# MEMS_BMI.net
KiCad netlist of a schematic drawn in EAGLE
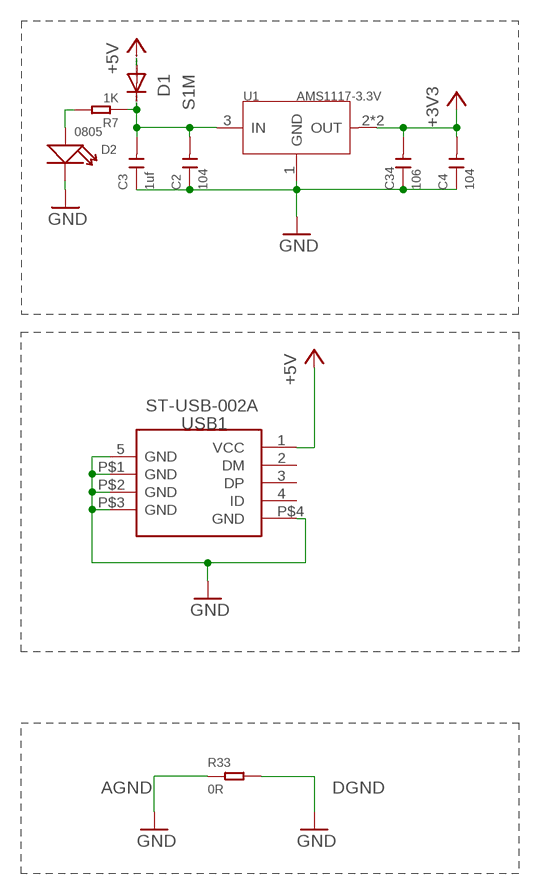
[diagram p0: schematic, sheet 1]
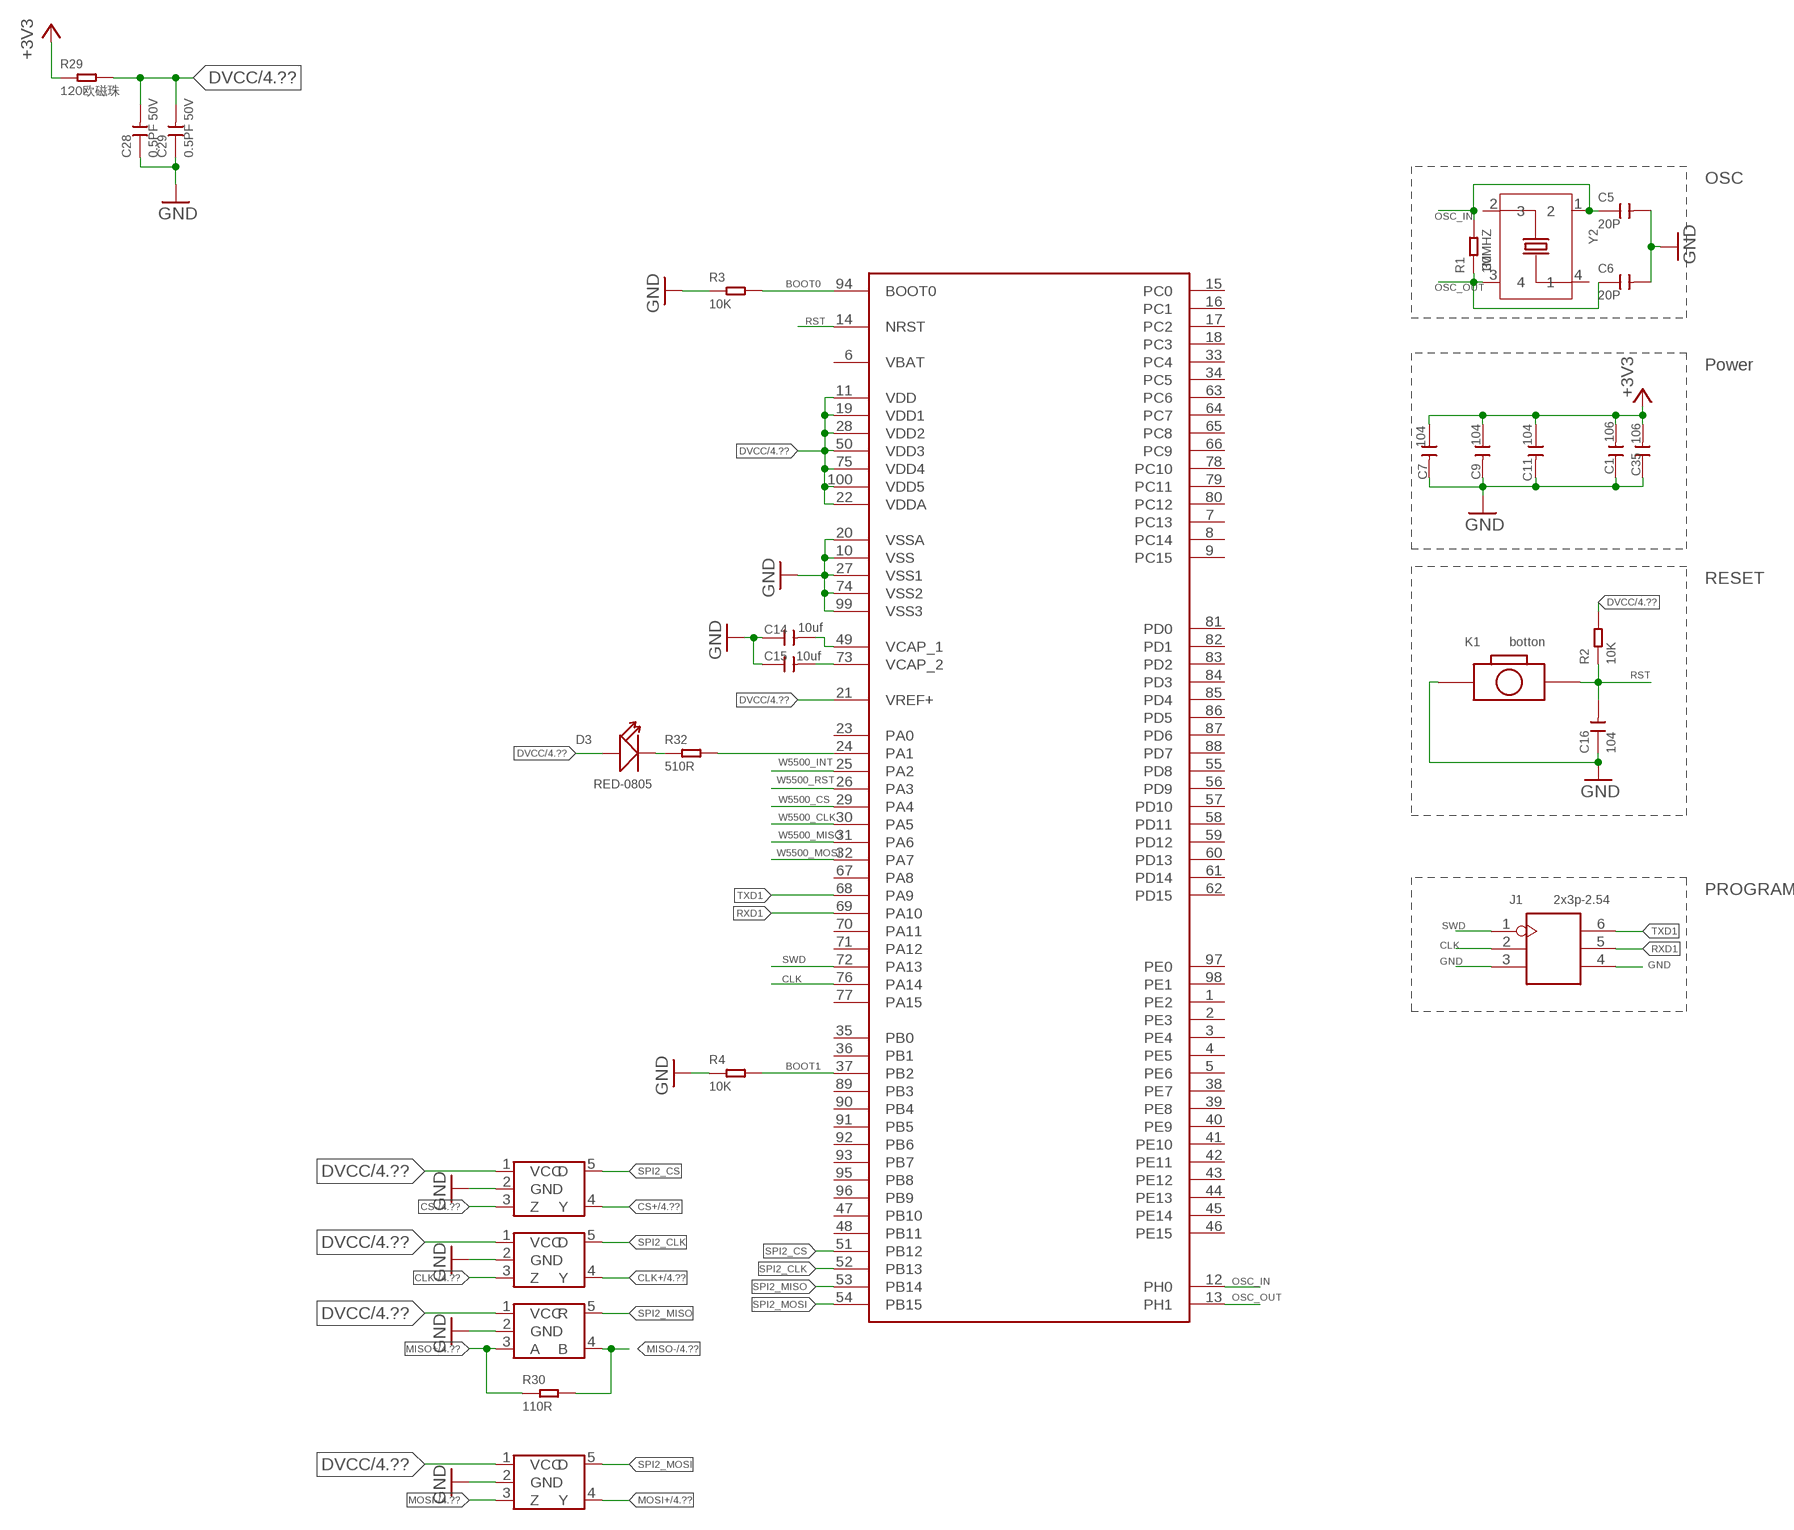
[diagram p1: schematic, sheet 2]
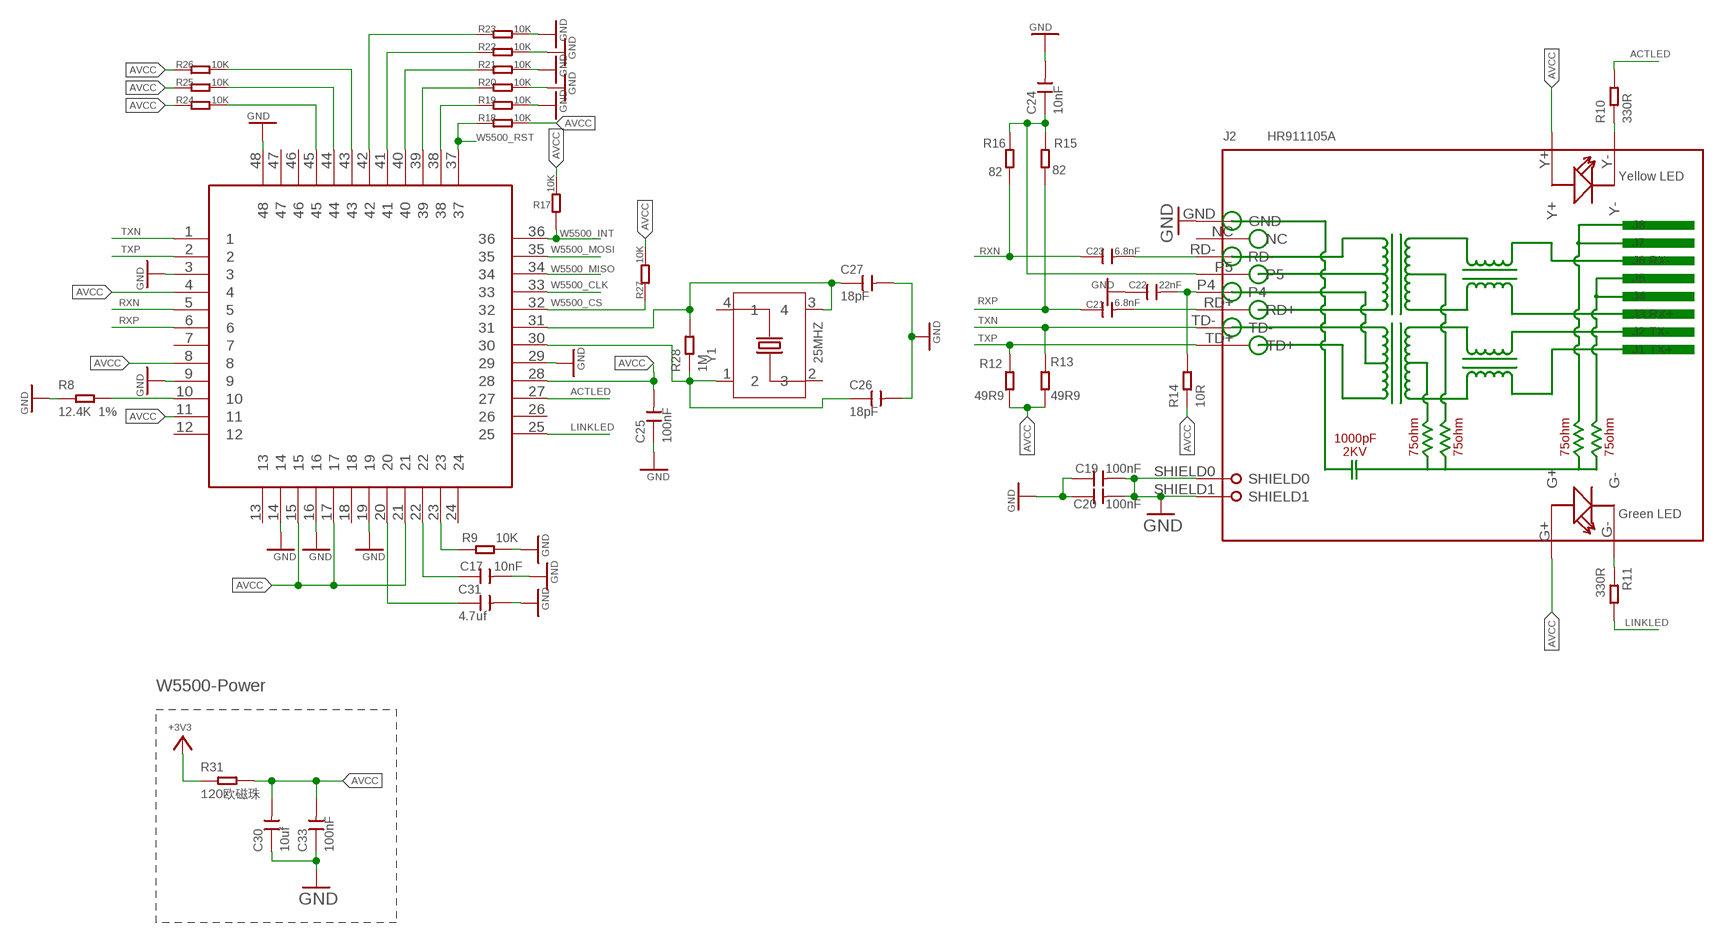
[diagram p2: schematic, sheet 3]
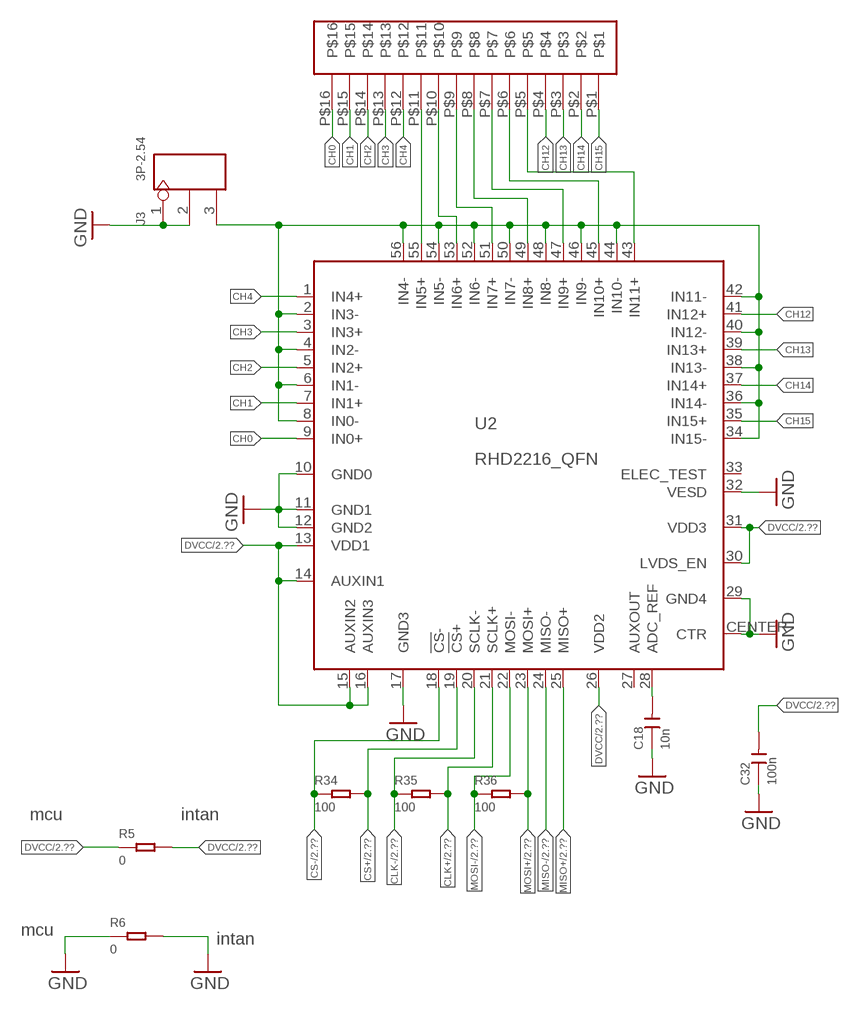
[diagram p3: schematic, sheet 4]

(export (version "E")
  (design (tool "Eeschema 10.0.6"))
  (components
    (comp (ref "C2")
      (value "104")
      (footprint "eagle-import:C0603")
      (libsource (lib "eagle-import") (part "CAP-(0603)"))
    )
    (comp (ref "C3")
      (value "1uf")
      (footprint "eagle-import:C0805")
      (fields (field (name "MPN") "CC0805KKX7R8BB105"))
      (libsource (lib "eagle-import") (part "CERAMIC-1UF-25V-10%-X7R(0805)"))
    )
    (comp (ref "C4")
      (value "104")
      (footprint "eagle-import:C0603")
      (libsource (lib "eagle-import") (part "CAP-(0603)"))
    )
    (comp (ref "C34")
      (value "106")
      (footprint "eagle-import:C0805")
      (fields (field (name "MPN") "CC0805KKX7R8BB105"))
      (libsource (lib "eagle-import") (part "CERAMIC-1UF-25V-10%-X7R(0805)"))
    )
    (comp (ref "D1")
      (value "S1M")
      (footprint "eagle-import:SMA")
      (libsource (lib "eagle-import") (part "S1M"))
    )
    (comp (ref "D2")
      (value "0805")
      (footprint "eagle-import:LED-0805")
      (fields (field (name "MPN") "17-215SURC/S530-A2/TR8"))
      (libsource (lib "eagle-import") (part "SMD-LED-CLEAR-RED(0805)"))
    )
    (comp (ref "R7")
      (value "1K")
      (footprint "eagle-import:R0603")
      (fields (field (name "MPN") "RC0603FR-071M1L"))
      (libsource (lib "eagle-import") (part "RES-(0603)"))
    )
    (comp (ref "R33")
      (value "0R")
      (footprint "eagle-import:R0603")
      (fields (field (name "MPN") "RC0603FR-071M1L"))
      (libsource (lib "eagle-import") (part "RES-(0603)"))
    )
    (comp (ref "U1")
      (value "AMS1117-3.3V")
      (footprint "eagle-import:SOT-223")
      (fields (field (name "MPN") "CJT1117-3.3"))
      (libsource (lib "eagle-import") (part "PMIC-CJT1117-3.3(SOT223)"))
    )
    (comp (ref "USB1")
      (value "ST-USB-002A")
      (footprint "eagle-import:MINIUSB5+4P-SMD-0.8-90D")
      (libsource (lib "eagle-import") (part "MINI-USB-RCPT-B-5PS-R/A-SMD(ST-USB-002A)"))
    )
    (comp (ref "C18")
      (value "10n")
      (footprint "eagle-import:C0603")
      (libsource (lib "eagle-import") (part "CAP-(0603)"))
    )
    (comp (ref "C32")
      (value "100n")
      (footprint "eagle-import:C0603")
      (libsource (lib "eagle-import") (part "CAP-(0603)"))
    )
    (comp (ref "J3")
      (value "3P-2.54")
      (footprint "eagle-import:H3-2.54")
      (fields (field (name "MPN") "P125-1103A0BS116A1"))
      (libsource (lib "eagle-import") (part "DIP-WHITE-MALE-HEADER-VERT(3P-2.54)"))
    )
    (comp (ref "R5")
      (value "0")
      (footprint "eagle-import:R0603")
      (fields (field (name "MPN") "RC0603FR-071M1L"))
      (libsource (lib "eagle-import") (part "RES-(0603)"))
    )
    (comp (ref "R6")
      (value "0")
      (footprint "eagle-import:R0603")
      (fields (field (name "MPN") "RC0603FR-071M1L"))
      (libsource (lib "eagle-import") (part "RES-(0603)"))
    )
    (comp (ref "R34")
      (value "100")
      (footprint "eagle-import:R0603")
      (fields (field (name "MPN") "RC0603FR-071M1L"))
      (libsource (lib "eagle-import") (part "RES-(0603)"))
    )
    (comp (ref "R35")
      (value "100")
      (footprint "eagle-import:R0603")
      (fields (field (name "MPN") "RC0603FR-071M1L"))
      (libsource (lib "eagle-import") (part "RES-(0603)"))
    )
    (comp (ref "R36")
      (value "100")
      (footprint "eagle-import:R0603")
      (fields (field (name "MPN") "RC0603FR-071M1L"))
      (libsource (lib "eagle-import") (part "RES-(0603)"))
    )
    (comp (ref "U$3")
      (value "PROBE")
      (footprint "eagle-import:PROBE-16-PIN")
      (libsource (lib "eagle-import") (part "PROBE"))
    )
    (comp (ref "U2")
      (value "RHD2216_QFN")
      (footprint "eagle-import:QFN56_8_X_8_LARGE")
      (libsource (lib "eagle-import") (part "RHD2216_QFN"))
    )
    (comp (ref "C17")
      (value "10nF")
      (footprint "eagle-import:C0603")
      (libsource (lib "eagle-import") (part "CAP-(0603)"))
    )
    (comp (ref "C19")
      (value "100nF")
      (footprint "eagle-import:C0603")
      (libsource (lib "eagle-import") (part "CAP-(0603)"))
    )
    (comp (ref "C20")
      (value "100nF")
      (footprint "eagle-import:C0603")
      (libsource (lib "eagle-import") (part "CAP-(0603)"))
    )
    (comp (ref "C21")
      (value "6.8nF")
      (footprint "eagle-import:C0603")
      (libsource (lib "eagle-import") (part "CAP-(0603)"))
    )
    (comp (ref "C22")
      (value "22nF")
      (footprint "eagle-import:C0603")
      (libsource (lib "eagle-import") (part "CAP-(0603)"))
    )
    (comp (ref "C23")
      (value "6.8nF")
      (footprint "eagle-import:C0603")
      (libsource (lib "eagle-import") (part "CAP-(0603)"))
    )
    (comp (ref "C24")
      (value "10nF")
      (footprint "eagle-import:C0603")
      (libsource (lib "eagle-import") (part "CAP-(0603)"))
    )
    (comp (ref "C25")
      (value "100nF")
      (footprint "eagle-import:C0603")
      (libsource (lib "eagle-import") (part "CAP-(0603)"))
    )
    (comp (ref "C26")
      (value "18pF")
      (footprint "eagle-import:C0603")
      (libsource (lib "eagle-import") (part "CAP-(0603)"))
    )
    (comp (ref "C27")
      (value "18pF")
      (footprint "eagle-import:C0603")
      (libsource (lib "eagle-import") (part "CAP-(0603)"))
    )
    (comp (ref "C30")
      (value "10uf")
      (footprint "eagle-import:C0805")
      (fields (field (name "MPN") "CC0805KKX7R8BB105"))
      (libsource (lib "eagle-import") (part "CERAMIC-1UF-25V-10%-X7R(0805)"))
    )
    (comp (ref "C31")
      (value "4.7uf")
      (footprint "eagle-import:C0805")
      (fields (field (name "MPN") "CC0805KKX7R8BB105"))
      (libsource (lib "eagle-import") (part "CERAMIC-1UF-25V-10%-X7R(0805)"))
    )
    (comp (ref "C33")
      (value "100nF")
      (footprint "eagle-import:C0603")
      (libsource (lib "eagle-import") (part "CAP-(0603)"))
    )
    (comp (ref "J2")
      (value "HR911105A")
      (footprint "eagle-import:RJ45-12+2P-21.3X16.04X13.4MM")
      (libsource (lib "eagle-import") (part "DIP-RJ45-CONNECTOR(HR911105A)"))
    )
    (comp (ref "R8")
      (value "12.4K 1%")
      (footprint "eagle-import:R0603")
      (fields (field (name "MPN") "RC0603FR-071M1L"))
      (libsource (lib "eagle-import") (part "RES-(0603)"))
    )
    (comp (ref "R9")
      (value "10K")
      (footprint "eagle-import:R0603")
      (fields (field (name "MPN") "RC0603FR-071M1L"))
      (libsource (lib "eagle-import") (part "RES-(0603)"))
    )
    (comp (ref "R10")
      (value "330R")
      (footprint "eagle-import:R0603")
      (fields (field (name "MPN") "RC0603FR-071M1L"))
      (libsource (lib "eagle-import") (part "RES-(0603)"))
    )
    (comp (ref "R11")
      (value "330R")
      (footprint "eagle-import:R0603")
      (fields (field (name "MPN") "RC0603FR-071M1L"))
      (libsource (lib "eagle-import") (part "RES-(0603)"))
    )
    (comp (ref "R12")
      (value "49R9")
      (footprint "eagle-import:R0603")
      (fields (field (name "MPN") "RC0603FR-071M1L"))
      (libsource (lib "eagle-import") (part "RES-(0603)"))
    )
    (comp (ref "R13")
      (value "49R9")
      (footprint "eagle-import:R0603")
      (fields (field (name "MPN") "RC0603FR-071M1L"))
      (libsource (lib "eagle-import") (part "RES-(0603)"))
    )
    (comp (ref "R14")
      (value "10R")
      (footprint "eagle-import:R0603")
      (fields (field (name "MPN") "RC0603FR-071M1L"))
      (libsource (lib "eagle-import") (part "RES-(0603)"))
    )
    (comp (ref "R15")
      (value "82")
      (footprint "eagle-import:R0603")
      (fields (field (name "MPN") "RC0603FR-071M1L"))
      (libsource (lib "eagle-import") (part "RES-(0603)"))
    )
    (comp (ref "R16")
      (value "82")
      (footprint "eagle-import:R0603")
      (fields (field (name "MPN") "RC0603FR-071M1L"))
      (libsource (lib "eagle-import") (part "RES-(0603)"))
    )
    (comp (ref "R17")
      (value "10K")
      (footprint "eagle-import:R0603")
      (fields (field (name "MPN") "RC0603FR-071M1L"))
      (libsource (lib "eagle-import") (part "RES-(0603)"))
    )
    (comp (ref "R18")
      (value "10K")
      (footprint "eagle-import:R0603")
      (fields (field (name "MPN") "RC0603FR-071M1L"))
      (libsource (lib "eagle-import") (part "RES-(0603)"))
    )
    (comp (ref "R19")
      (value "10K")
      (footprint "eagle-import:R0603")
      (fields (field (name "MPN") "RC0603FR-071M1L"))
      (libsource (lib "eagle-import") (part "RES-(0603)"))
    )
    (comp (ref "R20")
      (value "10K")
      (footprint "eagle-import:R0603")
      (fields (field (name "MPN") "RC0603FR-071M1L"))
      (libsource (lib "eagle-import") (part "RES-(0603)"))
    )
    (comp (ref "R21")
      (value "10K")
      (footprint "eagle-import:R0603")
      (fields (field (name "MPN") "RC0603FR-071M1L"))
      (libsource (lib "eagle-import") (part "RES-(0603)"))
    )
    (comp (ref "R22")
      (value "10K")
      (footprint "eagle-import:R0603")
      (fields (field (name "MPN") "RC0603FR-071M1L"))
      (libsource (lib "eagle-import") (part "RES-(0603)"))
    )
    (comp (ref "R23")
      (value "10K")
      (footprint "eagle-import:R0603")
      (fields (field (name "MPN") "RC0603FR-071M1L"))
      (libsource (lib "eagle-import") (part "RES-(0603)"))
    )
    (comp (ref "R24")
      (value "10K")
      (footprint "eagle-import:R0603")
      (fields (field (name "MPN") "RC0603FR-071M1L"))
      (libsource (lib "eagle-import") (part "RES-(0603)"))
    )
    (comp (ref "R25")
      (value "10K")
      (footprint "eagle-import:R0603")
      (fields (field (name "MPN") "RC0603FR-071M1L"))
      (libsource (lib "eagle-import") (part "RES-(0603)"))
    )
    (comp (ref "R26")
      (value "10K")
      (footprint "eagle-import:R0603")
      (fields (field (name "MPN") "RC0603FR-071M1L"))
      (libsource (lib "eagle-import") (part "RES-(0603)"))
    )
    (comp (ref "R27")
      (value "10K")
      (footprint "eagle-import:R0603")
      (fields (field (name "MPN") "RC0603FR-071M1L"))
      (libsource (lib "eagle-import") (part "RES-(0603)"))
    )
    (comp (ref "R28")
      (value "1M")
      (footprint "eagle-import:R0603")
      (fields (field (name "MPN") "RC0603FR-071M1L"))
      (libsource (lib "eagle-import") (part "RES-(0603)"))
    )
    (comp (ref "R31")
      (value "120欧磁珠")
      (footprint "eagle-import:R0603")
      (fields (field (name "MPN") "RC0603FR-071M1L"))
      (libsource (lib "eagle-import") (part "RES-(0603)"))
    )
    (comp (ref "W5500-1")
      (value "W5500")
      (footprint "eagle-import:LQFP48")
      (libsource (lib "eagle-import") (part "W5500"))
    )
    (comp (ref "Y1")
      (value "25MHZ")
      (footprint "eagle-import:X4-SMD-3.2X2.5X0.7MM")
      (fields (field (name "MPN") "7M30000024"))
      (libsource (lib "eagle-import") (part "SMD-CRYSTAL-30MHZ-10PF-10PPM-60R(4P-3.2X2.5MM)"))
    )
    (comp (ref "C1")
      (value "106")
      (footprint "eagle-import:C0805")
      (fields (field (name "MPN") "CC0805KKX7R8BB105"))
      (libsource (lib "eagle-import") (part "CERAMIC-1UF-25V-10%-X7R(0805)"))
    )
    (comp (ref "C5")
      (value "20P")
      (footprint "eagle-import:C0603")
      (libsource (lib "eagle-import") (part "CAP-(0603)"))
    )
    (comp (ref "C6")
      (value "20P")
      (footprint "eagle-import:C0603")
      (libsource (lib "eagle-import") (part "CAP-(0603)"))
    )
    (comp (ref "C7")
      (value "104")
      (footprint "eagle-import:C0603")
      (libsource (lib "eagle-import") (part "CAP-(0603)"))
    )
    (comp (ref "C9")
      (value "104")
      (footprint "eagle-import:C0603")
      (libsource (lib "eagle-import") (part "CAP-(0603)"))
    )
    (comp (ref "C11")
      (value "104")
      (footprint "eagle-import:C0603")
      (libsource (lib "eagle-import") (part "CAP-(0603)"))
    )
    (comp (ref "C14")
      (value "10uf")
      (footprint "eagle-import:C0805")
      (fields (field (name "MPN") "CC0805KKX7R8BB105"))
      (libsource (lib "eagle-import") (part "CERAMIC-1UF-25V-10%-X7R(0805)"))
    )
    (comp (ref "C15")
      (value "10uf")
      (footprint "eagle-import:C0805")
      (fields (field (name "MPN") "CC0805KKX7R8BB105"))
      (libsource (lib "eagle-import") (part "CERAMIC-1UF-25V-10%-X7R(0805)"))
    )
    (comp (ref "C16")
      (value "104")
      (footprint "eagle-import:C0603")
      (libsource (lib "eagle-import") (part "CAP-(0603)"))
    )
    (comp (ref "C28")
      (value "0.5PF 50V")
      (footprint "eagle-import:C0603")
      (libsource (lib "eagle-import") (part "CAP-(0603)"))
    )
    (comp (ref "C29")
      (value "0.5PF 50V")
      (footprint "eagle-import:C0603")
      (libsource (lib "eagle-import") (part "CAP-(0603)"))
    )
    (comp (ref "C35")
      (value "106")
      (footprint "eagle-import:C0805")
      (fields (field (name "MPN") "CC0805KKX7R8BB105"))
      (libsource (lib "eagle-import") (part "CERAMIC-1UF-25V-10%-X7R(0805)"))
    )
    (comp (ref "D3")
      (value "RED-0805")
      (footprint "eagle-import:LED-0805")
      (fields (field (name "MPN") "17-215SURC/S530-A2/TR8"))
      (libsource (lib "eagle-import") (part "SMD-LED-CLEAR-RED(0805)"))
    )
    (comp (ref "J1")
      (value "2x3p-2.54")
      (footprint "eagle-import:H2X3-2.54")
      (fields (field (name "MPN") "F185-1203A1BSYA1"))
      (libsource (lib "eagle-import") (part "DIP-BLACK-FEMALE-HEADER-VERT(2X3P-2.54)"))
    )
    (comp (ref "K1")
      (value "botton")
      (footprint "eagle-import:SW2-SMD-3.0X6.0_2.5")
      (fields (field (name "MPN") "B3U-1000P"))
      (libsource (lib "eagle-import") (part "SMD-BUTTON"))
    )
    (comp (ref "LVDS1-1")
      (value "SN65LVDS1")
      (footprint "eagle-import:DBV_R-PDSO-G5")
      (libsource (lib "eagle-import") (part "SN65LVDS1"))
    )
    (comp (ref "LVDS1-2")
      (value "SN65LVDS1")
      (footprint "eagle-import:DBV_R-PDSO-G5")
      (libsource (lib "eagle-import") (part "SN65LVDS1"))
    )
    (comp (ref "LVDS1-3")
      (value "SN65LVDS1")
      (footprint "eagle-import:DBV_R-PDSO-G5")
      (libsource (lib "eagle-import") (part "SN65LVDS1"))
    )
    (comp (ref "R1")
      (value "1M")
      (footprint "eagle-import:R0603")
      (fields (field (name "MPN") "RC0603FR-071M1L"))
      (libsource (lib "eagle-import") (part "RES-(0603)"))
    )
    (comp (ref "R2")
      (value "10K")
      (footprint "eagle-import:R0603")
      (fields (field (name "MPN") "RC0603FR-071M1L"))
      (libsource (lib "eagle-import") (part "RES-(0603)"))
    )
    (comp (ref "R3")
      (value "10K")
      (footprint "eagle-import:R0603")
      (fields (field (name "MPN") "RC0603FR-071M1L"))
      (libsource (lib "eagle-import") (part "RES-(0603)"))
    )
    (comp (ref "R4")
      (value "10K")
      (footprint "eagle-import:R0603")
      (fields (field (name "MPN") "RC0603FR-071M1L"))
      (libsource (lib "eagle-import") (part "RES-(0603)"))
    )
    (comp (ref "R29")
      (value "120欧磁珠")
      (footprint "eagle-import:R0603")
      (fields (field (name "MPN") "RC0603FR-071M1L"))
      (libsource (lib "eagle-import") (part "RES-(0603)"))
    )
    (comp (ref "R30")
      (value "110R")
      (footprint "eagle-import:R0603")
      (fields (field (name "MPN") "RC0603FR-071M1L"))
      (libsource (lib "eagle-import") (part "RES-(0603)"))
    )
    (comp (ref "R32")
      (value "510R")
      (footprint "eagle-import:R0603")
      (fields (field (name "MPN") "RC0603FR-071M1L"))
      (libsource (lib "eagle-import") (part "RES-(0603)"))
    )
    (comp (ref "U$1")
      (value "STM32F40XSTM32D40X")
      (footprint "eagle-import:LQFP100")
      (libsource (lib "eagle-import") (part "STM32F40XSTM32D40X"))
    )
    (comp (ref "U$2")
      (value "SN65LVDS2")
      (footprint "eagle-import:DBV_R-PDSO-G5")
      (libsource (lib "eagle-import") (part "SN65LVDS2"))
    )
    (comp (ref "Y2")
      (value "30MHZ")
      (footprint "eagle-import:X4-SMD-3.2X2.5X0.7MM")
      (fields (field (name "MPN") "7M30000024"))
      (libsource (lib "eagle-import") (part "SMD-CRYSTAL-30MHZ-10PF-10PPM-60R(4P-3.2X2.5MM)"))
    )
  )
  (nets
    (net (code "1") (name "+3V3") (class "Default")
      (node (ref "C1") (pin "2") (pinfunction "2_2") (pintype "passive"))
      (node (ref "C11") (pin "1") (pinfunction "1_1") (pintype "passive"))
      (node (ref "C34") (pin "2") (pinfunction "2_2") (pintype "passive"))
      (node (ref "C35") (pin "2") (pinfunction "2_2") (pintype "passive"))
      (node (ref "C4") (pin "2") (pinfunction "2_2") (pintype "passive"))
      (node (ref "C7") (pin "1") (pinfunction "1_1") (pintype "passive"))
      (node (ref "C9") (pin "1") (pinfunction "1_1") (pintype "passive"))
      (node (ref "R29") (pin "1") (pinfunction "1_1") (pintype "passive"))
      (node (ref "R31") (pin "1") (pinfunction "1_1") (pintype "passive"))
      (node (ref "U1") (pin "2") (pinfunction "OUT_2") (pintype "bidirectional"))
      (node (ref "U1") (pin "TER") (pinfunction "OUT_TER") (pintype "bidirectional"))
    )
    (net (code "2") (name "+5V") (class "Default")
      (node (ref "D1") (pin "A") (pinfunction "A_A") (pintype "passive"))
      (node (ref "USB1") (pin "1") (pinfunction "VCC_1") (pintype "bidirectional"))
    )
    (net (code "3") (name "ACTLED") (class "Default")
      (node (ref "R10") (pin "2") (pinfunction "2_2") (pintype "passive"))
      (node (ref "W5500-1") (pin "27") (pinfunction "27_27") (pintype "bidirectional"))
    )
    (net (code "4") (name "AVCC") (class "Default")
      (node (ref "C25") (pin "2") (pinfunction "2_2") (pintype "passive"))
      (node (ref "C30") (pin "2") (pinfunction "2_2") (pintype "passive"))
      (node (ref "C33") (pin "2") (pinfunction "2_2") (pintype "passive"))
      (node (ref "J2") (pin "G+") (pinfunction "G+_G+") (pintype "bidirectional"))
      (node (ref "J2") (pin "Y+") (pinfunction "Y+_Y+") (pintype "bidirectional"))
      (node (ref "R12") (pin "1") (pinfunction "1_1") (pintype "passive"))
      (node (ref "R13") (pin "1") (pinfunction "1_1") (pintype "passive"))
      (node (ref "R14") (pin "1") (pinfunction "1_1") (pintype "passive"))
      (node (ref "R17") (pin "2") (pinfunction "2_2") (pintype "passive"))
      (node (ref "R18") (pin "2") (pinfunction "2_2") (pintype "passive"))
      (node (ref "R24") (pin "1") (pinfunction "1_1") (pintype "passive"))
      (node (ref "R25") (pin "1") (pinfunction "1_1") (pintype "passive"))
      (node (ref "R26") (pin "1") (pinfunction "1_1") (pintype "passive"))
      (node (ref "R27") (pin "2") (pinfunction "2_2") (pintype "passive"))
      (node (ref "R31") (pin "2") (pinfunction "2_2") (pintype "passive"))
      (node (ref "W5500-1") (pin "11") (pinfunction "11_11") (pintype "bidirectional"))
      (node (ref "W5500-1") (pin "15") (pinfunction "15_15") (pintype "bidirectional"))
      (node (ref "W5500-1") (pin "17") (pinfunction "17_17") (pintype "bidirectional"))
      (node (ref "W5500-1") (pin "21") (pinfunction "21_21") (pintype "bidirectional"))
      (node (ref "W5500-1") (pin "28") (pinfunction "28_28") (pintype "bidirectional"))
      (node (ref "W5500-1") (pin "4") (pinfunction "4_4") (pintype "bidirectional"))
      (node (ref "W5500-1") (pin "8") (pinfunction "8_8") (pintype "bidirectional"))
    )
    (net (code "5") (name "BOOT0") (class "Default")
      (node (ref "R3") (pin "2") (pinfunction "2_2") (pintype "passive"))
      (node (ref "U$1") (pin "94") (pinfunction "BOOT0_94") (pintype "bidirectional"))
    )
    (net (code "6") (name "BOOT1") (class "Default")
      (node (ref "R4") (pin "2") (pinfunction "2_2") (pintype "passive"))
      (node (ref "U$1") (pin "37") (pinfunction "PB2_37") (pintype "bidirectional"))
    )
    (net (code "7") (name "CH0") (class "Default")
      (node (ref "U$3") (pin "P$16") (pinfunction "P$16_P$16") (pintype "bidirectional"))
      (node (ref "U2") (pin "9") (pinfunction "IN0+_9") (pintype "input"))
    )
    (net (code "8") (name "CH1") (class "Default")
      (node (ref "U$3") (pin "P$15") (pinfunction "P$15_P$15") (pintype "bidirectional"))
      (node (ref "U2") (pin "7") (pinfunction "IN1+_7") (pintype "input"))
    )
    (net (code "9") (name "CH2") (class "Default")
      (node (ref "U$3") (pin "P$14") (pinfunction "P$14_P$14") (pintype "bidirectional"))
      (node (ref "U2") (pin "5") (pinfunction "IN2+_5") (pintype "input"))
    )
    (net (code "10") (name "CH3") (class "Default")
      (node (ref "U$3") (pin "P$13") (pinfunction "P$13_P$13") (pintype "bidirectional"))
      (node (ref "U2") (pin "3") (pinfunction "IN3+_3") (pintype "input"))
    )
    (net (code "11") (name "CH4") (class "Default")
      (node (ref "U$3") (pin "P$12") (pinfunction "P$12_P$12") (pintype "bidirectional"))
      (node (ref "U2") (pin "1") (pinfunction "IN4+_1") (pintype "input"))
    )
    (net (code "12") (name "CH12") (class "Default")
      (node (ref "U$3") (pin "P$4") (pinfunction "P$4_P$4") (pintype "bidirectional"))
      (node (ref "U2") (pin "41") (pinfunction "IN12+_41") (pintype "input"))
    )
    (net (code "13") (name "CH13") (class "Default")
      (node (ref "U$3") (pin "P$3") (pinfunction "P$3_P$3") (pintype "bidirectional"))
      (node (ref "U2") (pin "39") (pinfunction "IN13+_39") (pintype "input"))
    )
    (net (code "14") (name "CH14") (class "Default")
      (node (ref "U$3") (pin "P$2") (pinfunction "P$2_P$2") (pintype "bidirectional"))
      (node (ref "U2") (pin "37") (pinfunction "IN14+_37") (pintype "input"))
    )
    (net (code "15") (name "CH15") (class "Default")
      (node (ref "U$3") (pin "P$1") (pinfunction "P$1_P$1") (pintype "bidirectional"))
      (node (ref "U2") (pin "35") (pinfunction "IN15+_35") (pintype "input"))
    )
    (net (code "16") (name "CLK") (class "Default")
      (node (ref "J1") (pin "2") (pinfunction "2_2") (pintype "bidirectional"))
      (node (ref "U$1") (pin "76") (pinfunction "PA14_76") (pintype "bidirectional"))
    )
    (net (code "17") (name "CLK+") (class "Default")
      (node (ref "LVDS1-2") (pin "4") (pinfunction "Y_4") (pintype "bidirectional"))
      (node (ref "R35") (pin "2") (pinfunction "2_2") (pintype "passive"))
      (node (ref "U2") (pin "21") (pinfunction "SCLK+_21") (pintype "input"))
    )
    (net (code "18") (name "CLK-") (class "Default")
      (node (ref "LVDS1-2") (pin "3") (pinfunction "Z_3") (pintype "bidirectional"))
      (node (ref "R35") (pin "1") (pinfunction "1_1") (pintype "passive"))
      (node (ref "U2") (pin "20") (pinfunction "SCLK-_20") (pintype "input"))
    )
    (net (code "19") (name "CS+") (class "Default")
      (node (ref "LVDS1-1") (pin "4") (pinfunction "Y_4") (pintype "bidirectional"))
      (node (ref "R34") (pin "2") (pinfunction "2_2") (pintype "passive"))
      (node (ref "U2") (pin "19") (pinfunction "~{CS}+_19") (pintype "input"))
    )
    (net (code "20") (name "CS-") (class "Default")
      (node (ref "LVDS1-1") (pin "3") (pinfunction "Z_3") (pintype "bidirectional"))
      (node (ref "R34") (pin "1") (pinfunction "1_1") (pintype "passive"))
      (node (ref "U2") (pin "18") (pinfunction "~{CS}-_18") (pintype "input"))
    )
    (net (code "21") (name "DVCC") (class "Default")
      (node (ref "C28") (pin "2") (pinfunction "2_2") (pintype "passive"))
      (node (ref "C29") (pin "2") (pinfunction "2_2") (pintype "passive"))
      (node (ref "C32") (pin "2") (pinfunction "2_2") (pintype "passive"))
      (node (ref "D3") (pin "+") (pinfunction "+_+") (pintype "passive"))
      (node (ref "LVDS1-1") (pin "1") (pinfunction "VCC_1") (pintype "bidirectional"))
      (node (ref "LVDS1-2") (pin "1") (pinfunction "VCC_1") (pintype "bidirectional"))
      (node (ref "LVDS1-3") (pin "1") (pinfunction "VCC_1") (pintype "bidirectional"))
      (node (ref "R2") (pin "2") (pinfunction "2_2") (pintype "passive"))
      (node (ref "R29") (pin "2") (pinfunction "2_2") (pintype "passive"))
      (node (ref "R5") (pin "1") (pinfunction "1_1") (pintype "passive"))
      (node (ref "R5") (pin "2") (pinfunction "2_2") (pintype "passive"))
      (node (ref "U$1") (pin "100") (pinfunction "VDD5_100") (pintype "bidirectional"))
      (node (ref "U$1") (pin "11") (pinfunction "VDD_11") (pintype "bidirectional"))
      (node (ref "U$1") (pin "19") (pinfunction "VDD1_19") (pintype "bidirectional"))
      (node (ref "U$1") (pin "21") (pinfunction "VREF+_21") (pintype "bidirectional"))
      (node (ref "U$1") (pin "22") (pinfunction "VDDA_22") (pintype "bidirectional"))
      (node (ref "U$1") (pin "28") (pinfunction "VDD2_28") (pintype "bidirectional"))
      (node (ref "U$1") (pin "50") (pinfunction "VDD3_50") (pintype "bidirectional"))
      (node (ref "U$1") (pin "75") (pinfunction "VDD4_75") (pintype "bidirectional"))
      (node (ref "U$2") (pin "1") (pinfunction "VCC_1") (pintype "bidirectional"))
      (node (ref "U2") (pin "13") (pinfunction "VDD1_13") (pintype "power_in"))
      (node (ref "U2") (pin "14") (pinfunction "AUXIN1_14") (pintype "input"))
      (node (ref "U2") (pin "15") (pinfunction "AUXIN2_15") (pintype "input"))
      (node (ref "U2") (pin "16") (pinfunction "AUXIN3_16") (pintype "input"))
      (node (ref "U2") (pin "26") (pinfunction "VDD2_26") (pintype "power_in"))
      (node (ref "U2") (pin "30") (pinfunction "LVDS_EN_30") (pintype "input"))
      (node (ref "U2") (pin "31") (pinfunction "VDD3_31") (pintype "power_in"))
    )
    (net (code "22") (name "GND") (class "Default")
      (node (ref "C1") (pin "1") (pinfunction "1_1") (pintype "passive"))
      (node (ref "C11") (pin "2") (pinfunction "2_2") (pintype "passive"))
      (node (ref "C14") (pin "1") (pinfunction "1_1") (pintype "passive"))
      (node (ref "C15") (pin "1") (pinfunction "1_1") (pintype "passive"))
      (node (ref "C16") (pin "1") (pinfunction "1_1") (pintype "passive"))
      (node (ref "C17") (pin "2") (pinfunction "2_2") (pintype "passive"))
      (node (ref "C18") (pin "1") (pinfunction "1_1") (pintype "passive"))
      (node (ref "C19") (pin "1") (pinfunction "1_1") (pintype "passive"))
      (node (ref "C19") (pin "2") (pinfunction "2_2") (pintype "passive"))
      (node (ref "C2") (pin "1") (pinfunction "1_1") (pintype "passive"))
      (node (ref "C20") (pin "1") (pinfunction "1_1") (pintype "passive"))
      (node (ref "C20") (pin "2") (pinfunction "2_2") (pintype "passive"))
      (node (ref "C22") (pin "1") (pinfunction "1_1") (pintype "passive"))
      (node (ref "C24") (pin "2") (pinfunction "2_2") (pintype "passive"))
      (node (ref "C25") (pin "1") (pinfunction "1_1") (pintype "passive"))
      (node (ref "C26") (pin "2") (pinfunction "2_2") (pintype "passive"))
      (node (ref "C27") (pin "2") (pinfunction "2_2") (pintype "passive"))
      (node (ref "C28") (pin "1") (pinfunction "1_1") (pintype "passive"))
      (node (ref "C29") (pin "1") (pinfunction "1_1") (pintype "passive"))
      (node (ref "C3") (pin "1") (pinfunction "1_1") (pintype "passive"))
      (node (ref "C30") (pin "1") (pinfunction "1_1") (pintype "passive"))
      (node (ref "C31") (pin "2") (pinfunction "2_2") (pintype "passive"))
      (node (ref "C32") (pin "1") (pinfunction "1_1") (pintype "passive"))
      (node (ref "C33") (pin "1") (pinfunction "1_1") (pintype "passive"))
      (node (ref "C34") (pin "1") (pinfunction "1_1") (pintype "passive"))
      (node (ref "C35") (pin "1") (pinfunction "1_1") (pintype "passive"))
      (node (ref "C4") (pin "1") (pinfunction "1_1") (pintype "passive"))
      (node (ref "C5") (pin "2") (pinfunction "2_2") (pintype "passive"))
      (node (ref "C6") (pin "2") (pinfunction "2_2") (pintype "passive"))
      (node (ref "C7") (pin "2") (pinfunction "2_2") (pintype "passive"))
      (node (ref "C9") (pin "2") (pinfunction "2_2") (pintype "passive"))
      (node (ref "D2") (pin "-") (pinfunction "-_-") (pintype "passive"))
      (node (ref "J1") (pin "3") (pinfunction "3_3") (pintype "bidirectional"))
      (node (ref "J1") (pin "4") (pinfunction "4_4") (pintype "bidirectional"))
      (node (ref "J2") (pin "GND") (pinfunction "GND_GND") (pintype "bidirectional"))
      (node (ref "J2") (pin "SHIELD0") (pinfunction "SHIELD0_SHIELD0") (pintype "bidirectional"))
      (node (ref "J2") (pin "SHIELD1") (pinfunction "SHIELD1_SHIELD1") (pintype "bidirectional"))
      (node (ref "J3") (pin "1") (pinfunction "P$1_1") (pintype "bidirectional"))
      (node (ref "J3") (pin "2") (pinfunction "P$2_2") (pintype "bidirectional"))
      (node (ref "K1") (pin "1") (pinfunction "1_1") (pintype "bidirectional"))
      (node (ref "LVDS1-1") (pin "2") (pinfunction "GND_2") (pintype "bidirectional"))
      (node (ref "LVDS1-2") (pin "2") (pinfunction "GND_2") (pintype "bidirectional"))
      (node (ref "LVDS1-3") (pin "2") (pinfunction "GND_2") (pintype "bidirectional"))
      (node (ref "R19") (pin "2") (pinfunction "2_2") (pintype "passive"))
      (node (ref "R20") (pin "2") (pinfunction "2_2") (pintype "passive"))
      (node (ref "R21") (pin "2") (pinfunction "2_2") (pintype "passive"))
      (node (ref "R22") (pin "2") (pinfunction "2_2") (pintype "passive"))
      (node (ref "R23") (pin "2") (pinfunction "2_2") (pintype "passive"))
      (node (ref "R3") (pin "1") (pinfunction "1_1") (pintype "passive"))
      (node (ref "R33") (pin "1") (pinfunction "1_1") (pintype "passive"))
      (node (ref "R33") (pin "2") (pinfunction "2_2") (pintype "passive"))
      (node (ref "R4") (pin "1") (pinfunction "1_1") (pintype "passive"))
      (node (ref "R6") (pin "1") (pinfunction "1_1") (pintype "passive"))
      (node (ref "R6") (pin "2") (pinfunction "2_2") (pintype "passive"))
      (node (ref "R8") (pin "1") (pinfunction "1_1") (pintype "passive"))
      (node (ref "R9") (pin "2") (pinfunction "2_2") (pintype "passive"))
      (node (ref "U$1") (pin "10") (pinfunction "VSS_10") (pintype "bidirectional"))
      (node (ref "U$1") (pin "20") (pinfunction "VSSA_20") (pintype "bidirectional"))
      (node (ref "U$1") (pin "27") (pinfunction "VSS1_27") (pintype "bidirectional"))
      (node (ref "U$1") (pin "74") (pinfunction "VSS2_74") (pintype "bidirectional"))
      (node (ref "U$1") (pin "99") (pinfunction "VSS3_99") (pintype "bidirectional"))
      (node (ref "U$2") (pin "2") (pinfunction "GND_2") (pintype "bidirectional"))
      (node (ref "U1") (pin "1") (pinfunction "GND_1") (pintype "bidirectional"))
      (node (ref "U2") (pin "10") (pinfunction "GND0_10") (pintype "input"))
      (node (ref "U2") (pin "11") (pinfunction "GND1_11") (pintype "power_in"))
      (node (ref "U2") (pin "12") (pinfunction "GND2_12") (pintype "power_in"))
      (node (ref "U2") (pin "17") (pinfunction "GND3_17") (pintype "power_in"))
      (node (ref "U2") (pin "29") (pinfunction "GND4_29") (pintype "power_in"))
      (node (ref "U2") (pin "32") (pinfunction "VESD_32") (pintype "power_in"))
      (node (ref "U2") (pin "CENTER") (pinfunction "CTR_CENTER") (pintype "power_in"))
      (node (ref "USB1") (pin "5") (pinfunction "GND_5") (pintype "bidirectional"))
      (node (ref "USB1") (pin "P$1") (pinfunction "GND_P$1") (pintype "bidirectional"))
      (node (ref "USB1") (pin "P$2") (pinfunction "GND_P$2") (pintype "bidirectional"))
      (node (ref "USB1") (pin "P$3") (pinfunction "GND_P$3") (pintype "bidirectional"))
      (node (ref "USB1") (pin "P$4") (pinfunction "GND_P$4") (pintype "bidirectional"))
      (node (ref "W5500-1") (pin "14") (pinfunction "14_14") (pintype "bidirectional"))
      (node (ref "W5500-1") (pin "16") (pinfunction "16_16") (pintype "bidirectional"))
      (node (ref "W5500-1") (pin "19") (pinfunction "19_19") (pintype "bidirectional"))
      (node (ref "W5500-1") (pin "29") (pinfunction "29_29") (pintype "bidirectional"))
      (node (ref "W5500-1") (pin "3") (pinfunction "3_3") (pintype "bidirectional"))
      (node (ref "W5500-1") (pin "48") (pinfunction "48_48") (pintype "bidirectional"))
      (node (ref "W5500-1") (pin "9") (pinfunction "9_9") (pintype "bidirectional"))
    )
    (net (code "23") (name "LINKLED") (class "Default")
      (node (ref "R11") (pin "2") (pinfunction "2_2") (pintype "passive"))
      (node (ref "W5500-1") (pin "25") (pinfunction "25_25") (pintype "bidirectional"))
    )
    (net (code "24") (name "MISO+") (class "Default")
      (node (ref "R30") (pin "1") (pinfunction "1_1") (pintype "passive"))
      (node (ref "U$2") (pin "3") (pinfunction "A_3") (pintype "bidirectional"))
      (node (ref "U2") (pin "25") (pinfunction "MISO+_25") (pintype "output"))
    )
    (net (code "25") (name "MISO-") (class "Default")
      (node (ref "R30") (pin "2") (pinfunction "2_2") (pintype "passive"))
      (node (ref "U$2") (pin "4") (pinfunction "B_4") (pintype "bidirectional"))
      (node (ref "U2") (pin "24") (pinfunction "MISO-_24") (pintype "output"))
    )
    (net (code "26") (name "MOSI+") (class "Default")
      (node (ref "LVDS1-3") (pin "4") (pinfunction "Y_4") (pintype "bidirectional"))
      (node (ref "R36") (pin "2") (pinfunction "2_2") (pintype "passive"))
      (node (ref "U2") (pin "23") (pinfunction "MOSI+_23") (pintype "input"))
    )
    (net (code "27") (name "MOSI-") (class "Default")
      (node (ref "LVDS1-3") (pin "3") (pinfunction "Z_3") (pintype "bidirectional"))
      (node (ref "R36") (pin "1") (pinfunction "1_1") (pintype "passive"))
      (node (ref "U2") (pin "22") (pinfunction "MOSI-_22") (pintype "input"))
    )
    (net (code "28") (name "Net-(C17-Pad1)") (class "Default")
      (node (ref "C17") (pin "1") (pinfunction "1_1") (pintype "passive"))
      (node (ref "W5500-1") (pin "22") (pinfunction "22_22") (pintype "bidirectional"))
    )
    (net (code "29") (name "Net-(C21-Pad2)") (class "Default")
      (node (ref "C21") (pin "2") (pinfunction "2_2") (pintype "passive"))
      (node (ref "J2") (pin "RD+") (pinfunction "RD+_RD+") (pintype "bidirectional"))
    )
    (net (code "30") (name "Net-(C22-Pad2)") (class "Default")
      (node (ref "C22") (pin "2") (pinfunction "2_2") (pintype "passive"))
      (node (ref "J2") (pin "P4") (pinfunction "P4_P4") (pintype "bidirectional"))
      (node (ref "R14") (pin "2") (pinfunction "2_2") (pintype "passive"))
    )
    (net (code "31") (name "Net-(C23-Pad2)") (class "Default")
      (node (ref "C23") (pin "2") (pinfunction "2_2") (pintype "passive"))
      (node (ref "J2") (pin "RD-") (pinfunction "RD-_RD-") (pintype "bidirectional"))
    )
    (net (code "32") (name "Net-(C24-Pad1)") (class "Default")
      (node (ref "C24") (pin "1") (pinfunction "1_1") (pintype "passive"))
      (node (ref "J2") (pin "P5") (pinfunction "P5_P5") (pintype "bidirectional"))
      (node (ref "R15") (pin "2") (pinfunction "2_2") (pintype "passive"))
      (node (ref "R16") (pin "2") (pinfunction "2_2") (pintype "passive"))
    )
    (net (code "33") (name "Net-(C31-Pad1)") (class "Default")
      (node (ref "C31") (pin "1") (pinfunction "1_1") (pintype "passive"))
      (node (ref "W5500-1") (pin "20") (pinfunction "20_20") (pintype "bidirectional"))
    )
    (net (code "34") (name "Net-(D2-Pad+)") (class "Default")
      (node (ref "D2") (pin "+") (pinfunction "+_+") (pintype "passive"))
      (node (ref "R7") (pin "2") (pinfunction "2_2") (pintype "passive"))
    )
    (net (code "35") (name "Net-(D3-Pad-)") (class "Default")
      (node (ref "D3") (pin "-") (pinfunction "-_-") (pintype "passive"))
      (node (ref "R32") (pin "1") (pinfunction "1_1") (pintype "passive"))
    )
    (net (code "36") (name "Net-(J2-PadG-)") (class "Default")
      (node (ref "J2") (pin "G-") (pinfunction "G-_G-") (pintype "bidirectional"))
      (node (ref "R11") (pin "1") (pinfunction "1_1") (pintype "passive"))
    )
    (net (code "37") (name "Net-(J2-PadY-)") (class "Default")
      (node (ref "J2") (pin "Y-") (pinfunction "Y-_Y-") (pintype "bidirectional"))
      (node (ref "R10") (pin "1") (pinfunction "1_1") (pintype "passive"))
    )
    (net (code "38") (name "Net-(J3-P$3)") (class "Default")
      (node (ref "J3") (pin "3") (pinfunction "P$3_3") (pintype "bidirectional"))
      (node (ref "U2") (pin "2") (pinfunction "IN3-_2") (pintype "input"))
      (node (ref "U2") (pin "34") (pinfunction "IN15-_34") (pintype "input"))
      (node (ref "U2") (pin "36") (pinfunction "IN14-_36") (pintype "input"))
      (node (ref "U2") (pin "38") (pinfunction "IN13-_38") (pintype "input"))
      (node (ref "U2") (pin "4") (pinfunction "IN2-_4") (pintype "input"))
      (node (ref "U2") (pin "40") (pinfunction "IN12-_40") (pintype "input"))
      (node (ref "U2") (pin "42") (pinfunction "IN11-_42") (pintype "input"))
      (node (ref "U2") (pin "44") (pinfunction "IN10-_44") (pintype "input"))
      (node (ref "U2") (pin "46") (pinfunction "IN9-_46") (pintype "input"))
      (node (ref "U2") (pin "48") (pinfunction "IN8-_48") (pintype "input"))
      (node (ref "U2") (pin "50") (pinfunction "IN7-_50") (pintype "input"))
      (node (ref "U2") (pin "52") (pinfunction "IN6-_52") (pintype "input"))
      (node (ref "U2") (pin "54") (pinfunction "IN5-_54") (pintype "input"))
      (node (ref "U2") (pin "56") (pinfunction "IN4-_56") (pintype "input"))
      (node (ref "U2") (pin "6") (pinfunction "IN1-_6") (pintype "input"))
      (node (ref "U2") (pin "8") (pinfunction "IN0-_8") (pintype "input"))
    )
    (net (code "39") (name "Net-(R8-Pad2)") (class "Default")
      (node (ref "R8") (pin "2") (pinfunction "2_2") (pintype "passive"))
      (node (ref "W5500-1") (pin "10") (pinfunction "10_10") (pintype "bidirectional"))
    )
    (net (code "40") (name "Net-(R9-Pad1)") (class "Default")
      (node (ref "R9") (pin "1") (pinfunction "1_1") (pintype "passive"))
      (node (ref "W5500-1") (pin "23") (pinfunction "23_23") (pintype "bidirectional"))
    )
    (net (code "41") (name "Net-(R19-Pad1)") (class "Default")
      (node (ref "R19") (pin "1") (pinfunction "1_1") (pintype "passive"))
      (node (ref "W5500-1") (pin "38") (pinfunction "38_38") (pintype "bidirectional"))
    )
    (net (code "42") (name "Net-(R20-Pad1)") (class "Default")
      (node (ref "R20") (pin "1") (pinfunction "1_1") (pintype "passive"))
      (node (ref "W5500-1") (pin "39") (pinfunction "39_39") (pintype "bidirectional"))
    )
    (net (code "43") (name "Net-(R21-Pad1)") (class "Default")
      (node (ref "R21") (pin "1") (pinfunction "1_1") (pintype "passive"))
      (node (ref "W5500-1") (pin "40") (pinfunction "40_40") (pintype "bidirectional"))
    )
    (net (code "44") (name "Net-(R22-Pad1)") (class "Default")
      (node (ref "R22") (pin "1") (pinfunction "1_1") (pintype "passive"))
      (node (ref "W5500-1") (pin "41") (pinfunction "41_41") (pintype "bidirectional"))
    )
    (net (code "45") (name "Net-(R23-Pad1)") (class "Default")
      (node (ref "R23") (pin "1") (pinfunction "1_1") (pintype "passive"))
      (node (ref "W5500-1") (pin "42") (pinfunction "42_42") (pintype "bidirectional"))
    )
    (net (code "46") (name "Net-(R24-Pad2)") (class "Default")
      (node (ref "R24") (pin "2") (pinfunction "2_2") (pintype "passive"))
      (node (ref "W5500-1") (pin "45") (pinfunction "45_45") (pintype "bidirectional"))
    )
    (net (code "47") (name "Net-(R25-Pad2)") (class "Default")
      (node (ref "R25") (pin "2") (pinfunction "2_2") (pintype "passive"))
      (node (ref "W5500-1") (pin "44") (pinfunction "44_44") (pintype "bidirectional"))
    )
    (net (code "48") (name "Net-(R26-Pad2)") (class "Default")
      (node (ref "R26") (pin "2") (pinfunction "2_2") (pintype "passive"))
      (node (ref "W5500-1") (pin "43") (pinfunction "43_43") (pintype "bidirectional"))
    )
    (net (code "49") (name "Net-(U$1-PA1)") (class "Default")
      (node (ref "R32") (pin "2") (pinfunction "2_2") (pintype "passive"))
      (node (ref "U$1") (pin "24") (pinfunction "PA1_24") (pintype "bidirectional"))
    )
    (net (code "50") (name "Net-(U$1-VCAP_1)") (class "Default")
      (node (ref "C14") (pin "2") (pinfunction "2_2") (pintype "passive"))
      (node (ref "U$1") (pin "49") (pinfunction "VCAP_1_49") (pintype "bidirectional"))
    )
    (net (code "51") (name "Net-(U$1-VCAP_2)") (class "Default")
      (node (ref "C15") (pin "2") (pinfunction "2_2") (pintype "passive"))
      (node (ref "U$1") (pin "73") (pinfunction "VCAP_2_73") (pintype "bidirectional"))
    )
    (net (code "52") (name "Net-(U1-IN)") (class "Default")
      (node (ref "C2") (pin "2") (pinfunction "2_2") (pintype "passive"))
      (node (ref "C3") (pin "2") (pinfunction "2_2") (pintype "passive"))
      (node (ref "D1") (pin "C") (pinfunction "C_C") (pintype "passive"))
      (node (ref "R7") (pin "1") (pinfunction "1_1") (pintype "passive"))
      (node (ref "U1") (pin "3") (pinfunction "IN_3") (pintype "bidirectional"))
    )
    (net (code "53") (name "Net-(U2-ADC_REF)") (class "Default")
      (node (ref "C18") (pin "2") (pinfunction "2_2") (pintype "passive"))
      (node (ref "U2") (pin "28") (pinfunction "ADC_REF_28") (pintype "passive"))
    )
    (net (code "54") (name "Net-(U2-IN5+)") (class "Default")
      (node (ref "U$3") (pin "P$11") (pinfunction "P$11_P$11") (pintype "bidirectional"))
      (node (ref "U2") (pin "55") (pinfunction "IN5+_55") (pintype "input"))
    )
    (net (code "55") (name "Net-(U2-IN6+)") (class "Default")
      (node (ref "U$3") (pin "P$10") (pinfunction "P$10_P$10") (pintype "bidirectional"))
      (node (ref "U2") (pin "53") (pinfunction "IN6+_53") (pintype "input"))
    )
    (net (code "56") (name "Net-(U2-IN7+)") (class "Default")
      (node (ref "U$3") (pin "P$9") (pinfunction "P$9_P$9") (pintype "bidirectional"))
      (node (ref "U2") (pin "51") (pinfunction "IN7+_51") (pintype "input"))
    )
    (net (code "57") (name "Net-(U2-IN8+)") (class "Default")
      (node (ref "U$3") (pin "P$8") (pinfunction "P$8_P$8") (pintype "bidirectional"))
      (node (ref "U2") (pin "49") (pinfunction "IN8+_49") (pintype "input"))
    )
    (net (code "58") (name "Net-(U2-IN9+)") (class "Default")
      (node (ref "U$3") (pin "P$7") (pinfunction "P$7_P$7") (pintype "bidirectional"))
      (node (ref "U2") (pin "47") (pinfunction "IN9+_47") (pintype "input"))
    )
    (net (code "59") (name "Net-(U2-IN10+)") (class "Default")
      (node (ref "U$3") (pin "P$6") (pinfunction "P$6_P$6") (pintype "bidirectional"))
      (node (ref "U2") (pin "45") (pinfunction "IN10+_45") (pintype "input"))
    )
    (net (code "60") (name "Net-(U2-IN11+)") (class "Default")
      (node (ref "U$3") (pin "P$5") (pinfunction "P$5_P$5") (pintype "bidirectional"))
      (node (ref "U2") (pin "43") (pinfunction "IN11+_43") (pintype "input"))
    )
    (net (code "61") (name "Net-(Y1-2)") (class "Default")
      (node (ref "C26") (pin "1") (pinfunction "1_1") (pintype "passive"))
      (node (ref "R28") (pin "1") (pinfunction "1_1") (pintype "passive"))
      (node (ref "W5500-1") (pin "30") (pinfunction "30_30") (pintype "bidirectional"))
      (node (ref "Y1") (pin "1") (pinfunction "2_1") (pintype "bidirectional"))
    )
    (net (code "62") (name "Net-(Y1-4)") (class "Default")
      (node (ref "C27") (pin "1") (pinfunction "1_1") (pintype "passive"))
      (node (ref "R28") (pin "2") (pinfunction "2_2") (pintype "passive"))
      (node (ref "W5500-1") (pin "31") (pinfunction "31_31") (pintype "bidirectional"))
      (node (ref "Y1") (pin "3") (pinfunction "4_3") (pintype "bidirectional"))
    )
    (net (code "63") (name "OSC_IN") (class "Default")
      (node (ref "C5") (pin "1") (pinfunction "1_1") (pintype "passive"))
      (node (ref "R1") (pin "2") (pinfunction "2_2") (pintype "passive"))
      (node (ref "U$1") (pin "12") (pinfunction "PH0_12") (pintype "bidirectional"))
      (node (ref "Y2") (pin "1") (pinfunction "2_1") (pintype "bidirectional"))
    )
    (net (code "64") (name "OSC_OUT") (class "Default")
      (node (ref "C6") (pin "1") (pinfunction "1_1") (pintype "passive"))
      (node (ref "R1") (pin "1") (pinfunction "1_1") (pintype "passive"))
      (node (ref "U$1") (pin "13") (pinfunction "PH1_13") (pintype "bidirectional"))
      (node (ref "Y2") (pin "3") (pinfunction "4_3") (pintype "bidirectional"))
    )
    (net (code "65") (name "RST") (class "Default")
      (node (ref "C16") (pin "2") (pinfunction "2_2") (pintype "passive"))
      (node (ref "K1") (pin "2") (pinfunction "2_2") (pintype "bidirectional"))
      (node (ref "R2") (pin "1") (pinfunction "1_1") (pintype "passive"))
      (node (ref "U$1") (pin "14") (pinfunction "NRST_14") (pintype "bidirectional"))
    )
    (net (code "66") (name "RXD1") (class "Default")
      (node (ref "J1") (pin "5") (pinfunction "5_5") (pintype "bidirectional"))
      (node (ref "U$1") (pin "69") (pinfunction "PA10_69") (pintype "bidirectional"))
    )
    (net (code "67") (name "RXN") (class "Default")
      (node (ref "C23") (pin "1") (pinfunction "1_1") (pintype "passive"))
      (node (ref "R16") (pin "1") (pinfunction "1_1") (pintype "passive"))
      (node (ref "W5500-1") (pin "5") (pinfunction "5_5") (pintype "bidirectional"))
    )
    (net (code "68") (name "RXP") (class "Default")
      (node (ref "C21") (pin "1") (pinfunction "1_1") (pintype "passive"))
      (node (ref "R15") (pin "1") (pinfunction "1_1") (pintype "passive"))
      (node (ref "W5500-1") (pin "6") (pinfunction "6_6") (pintype "bidirectional"))
    )
    (net (code "69") (name "SPI2_CLK") (class "Default")
      (node (ref "LVDS1-2") (pin "5") (pinfunction "D_5") (pintype "bidirectional"))
      (node (ref "U$1") (pin "52") (pinfunction "PB13_52") (pintype "bidirectional"))
    )
    (net (code "70") (name "SPI2_CS") (class "Default")
      (node (ref "LVDS1-1") (pin "5") (pinfunction "D_5") (pintype "bidirectional"))
      (node (ref "U$1") (pin "51") (pinfunction "PB12_51") (pintype "bidirectional"))
    )
    (net (code "71") (name "SPI2_MISO") (class "Default")
      (node (ref "U$1") (pin "53") (pinfunction "PB14_53") (pintype "bidirectional"))
      (node (ref "U$2") (pin "5") (pinfunction "R_5") (pintype "bidirectional"))
    )
    (net (code "72") (name "SPI2_MOSI") (class "Default")
      (node (ref "LVDS1-3") (pin "5") (pinfunction "D_5") (pintype "bidirectional"))
      (node (ref "U$1") (pin "54") (pinfunction "PB15_54") (pintype "bidirectional"))
    )
    (net (code "73") (name "SWD") (class "Default")
      (node (ref "J1") (pin "1") (pinfunction "1_1") (pintype "bidirectional"))
      (node (ref "U$1") (pin "72") (pinfunction "PA13_72") (pintype "bidirectional"))
    )
    (net (code "74") (name "TXD1") (class "Default")
      (node (ref "J1") (pin "6") (pinfunction "6_6") (pintype "bidirectional"))
      (node (ref "U$1") (pin "68") (pinfunction "PA9_68") (pintype "bidirectional"))
    )
    (net (code "75") (name "TXN") (class "Default")
      (node (ref "J2") (pin "TD-") (pinfunction "TD-_TD-") (pintype "bidirectional"))
      (node (ref "R13") (pin "2") (pinfunction "2_2") (pintype "passive"))
      (node (ref "W5500-1") (pin "1") (pinfunction "1_1") (pintype "bidirectional"))
    )
    (net (code "76") (name "TXP") (class "Default")
      (node (ref "J2") (pin "TD+") (pinfunction "TD+_TD+") (pintype "bidirectional"))
      (node (ref "R12") (pin "2") (pinfunction "2_2") (pintype "passive"))
      (node (ref "W5500-1") (pin "2") (pinfunction "2_2") (pintype "bidirectional"))
    )
    (net (code "77") (name "W5500_CLK") (class "Default")
      (node (ref "U$1") (pin "30") (pinfunction "PA5_30") (pintype "bidirectional"))
      (node (ref "W5500-1") (pin "33") (pinfunction "33_33") (pintype "bidirectional"))
    )
    (net (code "78") (name "W5500_CS") (class "Default")
      (node (ref "R27") (pin "1") (pinfunction "1_1") (pintype "passive"))
      (node (ref "U$1") (pin "29") (pinfunction "PA4_29") (pintype "bidirectional"))
      (node (ref "W5500-1") (pin "32") (pinfunction "32_32") (pintype "bidirectional"))
    )
    (net (code "79") (name "W5500_INT") (class "Default")
      (node (ref "R17") (pin "1") (pinfunction "1_1") (pintype "passive"))
      (node (ref "U$1") (pin "25") (pinfunction "PA2_25") (pintype "bidirectional"))
      (node (ref "W5500-1") (pin "36") (pinfunction "36_36") (pintype "bidirectional"))
    )
    (net (code "80") (name "W5500_MISO") (class "Default")
      (node (ref "U$1") (pin "31") (pinfunction "PA6_31") (pintype "bidirectional"))
      (node (ref "W5500-1") (pin "34") (pinfunction "34_34") (pintype "bidirectional"))
    )
    (net (code "81") (name "W5500_MOSI") (class "Default")
      (node (ref "U$1") (pin "32") (pinfunction "PA7_32") (pintype "bidirectional"))
      (node (ref "W5500-1") (pin "35") (pinfunction "35_35") (pintype "bidirectional"))
    )
    (net (code "82") (name "W5500_RST") (class "Default")
      (node (ref "R18") (pin "1") (pinfunction "1_1") (pintype "passive"))
      (node (ref "U$1") (pin "26") (pinfunction "PA3_26") (pintype "bidirectional"))
      (node (ref "W5500-1") (pin "37") (pinfunction "37_37") (pintype "bidirectional"))
    )
    (net (code "83") (name "unconnected-(J2-PadNC)") (class "Default")
      (node (ref "J2") (pin "NC") (pinfunction "NC_NC") (pintype "bidirectional"))
    )
    (net (code "84") (name "unconnected-(U$1-PA0-Pad23)") (class "Default")
      (node (ref "U$1") (pin "23") (pinfunction "PA0_23") (pintype "bidirectional"))
    )
    (net (code "85") (name "unconnected-(U$1-PA8-Pad67)") (class "Default")
      (node (ref "U$1") (pin "67") (pinfunction "PA8_67") (pintype "bidirectional"))
    )
    (net (code "86") (name "unconnected-(U$1-PA11-Pad70)") (class "Default")
      (node (ref "U$1") (pin "70") (pinfunction "PA11_70") (pintype "bidirectional"))
    )
    (net (code "87") (name "unconnected-(U$1-PA12-Pad71)") (class "Default")
      (node (ref "U$1") (pin "71") (pinfunction "PA12_71") (pintype "bidirectional"))
    )
    (net (code "88") (name "unconnected-(U$1-PA15-Pad77)") (class "Default")
      (node (ref "U$1") (pin "77") (pinfunction "PA15_77") (pintype "bidirectional"))
    )
    (net (code "89") (name "unconnected-(U$1-PB0-Pad35)") (class "Default")
      (node (ref "U$1") (pin "35") (pinfunction "PB0_35") (pintype "bidirectional"))
    )
    (net (code "90") (name "unconnected-(U$1-PB1-Pad36)") (class "Default")
      (node (ref "U$1") (pin "36") (pinfunction "PB1_36") (pintype "bidirectional"))
    )
    (net (code "91") (name "unconnected-(U$1-PB3-Pad89)") (class "Default")
      (node (ref "U$1") (pin "89") (pinfunction "PB3_89") (pintype "bidirectional"))
    )
    (net (code "92") (name "unconnected-(U$1-PB4-Pad90)") (class "Default")
      (node (ref "U$1") (pin "90") (pinfunction "PB4_90") (pintype "bidirectional"))
    )
    (net (code "93") (name "unconnected-(U$1-PB5-Pad91)") (class "Default")
      (node (ref "U$1") (pin "91") (pinfunction "PB5_91") (pintype "bidirectional"))
    )
    (net (code "94") (name "unconnected-(U$1-PB6-Pad92)") (class "Default")
      (node (ref "U$1") (pin "92") (pinfunction "PB6_92") (pintype "bidirectional"))
    )
    (net (code "95") (name "unconnected-(U$1-PB7-Pad93)") (class "Default")
      (node (ref "U$1") (pin "93") (pinfunction "PB7_93") (pintype "bidirectional"))
    )
    (net (code "96") (name "unconnected-(U$1-PB8-Pad95)") (class "Default")
      (node (ref "U$1") (pin "95") (pinfunction "PB8_95") (pintype "bidirectional"))
    )
    (net (code "97") (name "unconnected-(U$1-PB9-Pad96)") (class "Default")
      (node (ref "U$1") (pin "96") (pinfunction "PB9_96") (pintype "bidirectional"))
    )
    (net (code "98") (name "unconnected-(U$1-PB10-Pad47)") (class "Default")
      (node (ref "U$1") (pin "47") (pinfunction "PB10_47") (pintype "bidirectional"))
    )
    (net (code "99") (name "unconnected-(U$1-PB11-Pad48)") (class "Default")
      (node (ref "U$1") (pin "48") (pinfunction "PB11_48") (pintype "bidirectional"))
    )
    (net (code "100") (name "unconnected-(U$1-PC0-Pad15)") (class "Default")
      (node (ref "U$1") (pin "15") (pinfunction "PC0_15") (pintype "bidirectional"))
    )
    (net (code "101") (name "unconnected-(U$1-PC1-Pad16)") (class "Default")
      (node (ref "U$1") (pin "16") (pinfunction "PC1_16") (pintype "bidirectional"))
    )
    (net (code "102") (name "unconnected-(U$1-PC2-Pad17)") (class "Default")
      (node (ref "U$1") (pin "17") (pinfunction "PC2_17") (pintype "bidirectional"))
    )
    (net (code "103") (name "unconnected-(U$1-PC3-Pad18)") (class "Default")
      (node (ref "U$1") (pin "18") (pinfunction "PC3_18") (pintype "bidirectional"))
    )
    (net (code "104") (name "unconnected-(U$1-PC4-Pad33)") (class "Default")
      (node (ref "U$1") (pin "33") (pinfunction "PC4_33") (pintype "bidirectional"))
    )
    (net (code "105") (name "unconnected-(U$1-PC5-Pad34)") (class "Default")
      (node (ref "U$1") (pin "34") (pinfunction "PC5_34") (pintype "bidirectional"))
    )
    (net (code "106") (name "unconnected-(U$1-PC6-Pad63)") (class "Default")
      (node (ref "U$1") (pin "63") (pinfunction "PC6_63") (pintype "bidirectional"))
    )
    (net (code "107") (name "unconnected-(U$1-PC7-Pad64)") (class "Default")
      (node (ref "U$1") (pin "64") (pinfunction "PC7_64") (pintype "bidirectional"))
    )
    (net (code "108") (name "unconnected-(U$1-PC8-Pad65)") (class "Default")
      (node (ref "U$1") (pin "65") (pinfunction "PC8_65") (pintype "bidirectional"))
    )
    (net (code "109") (name "unconnected-(U$1-PC9-Pad66)") (class "Default")
      (node (ref "U$1") (pin "66") (pinfunction "PC9_66") (pintype "bidirectional"))
    )
    (net (code "110") (name "unconnected-(U$1-PC10-Pad78)") (class "Default")
      (node (ref "U$1") (pin "78") (pinfunction "PC10_78") (pintype "bidirectional"))
    )
    (net (code "111") (name "unconnected-(U$1-PC11-Pad79)") (class "Default")
      (node (ref "U$1") (pin "79") (pinfunction "PC11_79") (pintype "bidirectional"))
    )
    (net (code "112") (name "unconnected-(U$1-PC12-Pad80)") (class "Default")
      (node (ref "U$1") (pin "80") (pinfunction "PC12_80") (pintype "bidirectional"))
    )
    (net (code "113") (name "unconnected-(U$1-PC13-Pad7)") (class "Default")
      (node (ref "U$1") (pin "7") (pinfunction "PC13_7") (pintype "bidirectional"))
    )
    (net (code "114") (name "unconnected-(U$1-PC14-Pad8)") (class "Default")
      (node (ref "U$1") (pin "8") (pinfunction "PC14_8") (pintype "bidirectional"))
    )
    (net (code "115") (name "unconnected-(U$1-PC15-Pad9)") (class "Default")
      (node (ref "U$1") (pin "9") (pinfunction "PC15_9") (pintype "bidirectional"))
    )
    (net (code "116") (name "unconnected-(U$1-PD0-Pad81)") (class "Default")
      (node (ref "U$1") (pin "81") (pinfunction "PD0_81") (pintype "bidirectional"))
    )
    (net (code "117") (name "unconnected-(U$1-PD1-Pad82)") (class "Default")
      (node (ref "U$1") (pin "82") (pinfunction "PD1_82") (pintype "bidirectional"))
    )
    (net (code "118") (name "unconnected-(U$1-PD2-Pad83)") (class "Default")
      (node (ref "U$1") (pin "83") (pinfunction "PD2_83") (pintype "bidirectional"))
    )
    (net (code "119") (name "unconnected-(U$1-PD3-Pad84)") (class "Default")
      (node (ref "U$1") (pin "84") (pinfunction "PD3_84") (pintype "bidirectional"))
    )
    (net (code "120") (name "unconnected-(U$1-PD4-Pad85)") (class "Default")
      (node (ref "U$1") (pin "85") (pinfunction "PD4_85") (pintype "bidirectional"))
    )
    (net (code "121") (name "unconnected-(U$1-PD5-Pad86)") (class "Default")
      (node (ref "U$1") (pin "86") (pinfunction "PD5_86") (pintype "bidirectional"))
    )
    (net (code "122") (name "unconnected-(U$1-PD6-Pad87)") (class "Default")
      (node (ref "U$1") (pin "87") (pinfunction "PD6_87") (pintype "bidirectional"))
    )
    (net (code "123") (name "unconnected-(U$1-PD7-Pad88)") (class "Default")
      (node (ref "U$1") (pin "88") (pinfunction "PD7_88") (pintype "bidirectional"))
    )
    (net (code "124") (name "unconnected-(U$1-PD8-Pad55)") (class "Default")
      (node (ref "U$1") (pin "55") (pinfunction "PD8_55") (pintype "bidirectional"))
    )
    (net (code "125") (name "unconnected-(U$1-PD9-Pad56)") (class "Default")
      (node (ref "U$1") (pin "56") (pinfunction "PD9_56") (pintype "bidirectional"))
    )
    (net (code "126") (name "unconnected-(U$1-PD10-Pad57)") (class "Default")
      (node (ref "U$1") (pin "57") (pinfunction "PD10_57") (pintype "bidirectional"))
    )
    (net (code "127") (name "unconnected-(U$1-PD11-Pad58)") (class "Default")
      (node (ref "U$1") (pin "58") (pinfunction "PD11_58") (pintype "bidirectional"))
    )
    (net (code "128") (name "unconnected-(U$1-PD12-Pad59)") (class "Default")
      (node (ref "U$1") (pin "59") (pinfunction "PD12_59") (pintype "bidirectional"))
    )
    (net (code "129") (name "unconnected-(U$1-PD13-Pad60)") (class "Default")
      (node (ref "U$1") (pin "60") (pinfunction "PD13_60") (pintype "bidirectional"))
    )
    (net (code "130") (name "unconnected-(U$1-PD14-Pad61)") (class "Default")
      (node (ref "U$1") (pin "61") (pinfunction "PD14_61") (pintype "bidirectional"))
    )
    (net (code "131") (name "unconnected-(U$1-PD15-Pad62)") (class "Default")
      (node (ref "U$1") (pin "62") (pinfunction "PD15_62") (pintype "bidirectional"))
    )
    (net (code "132") (name "unconnected-(U$1-PE0-Pad97)") (class "Default")
      (node (ref "U$1") (pin "97") (pinfunction "PE0_97") (pintype "bidirectional"))
    )
    (net (code "133") (name "unconnected-(U$1-PE1-Pad98)") (class "Default")
      (node (ref "U$1") (pin "98") (pinfunction "PE1_98") (pintype "bidirectional"))
    )
    (net (code "134") (name "unconnected-(U$1-PE2-Pad1)") (class "Default")
      (node (ref "U$1") (pin "1") (pinfunction "PE2_1") (pintype "bidirectional"))
    )
    (net (code "135") (name "unconnected-(U$1-PE3-Pad2)") (class "Default")
      (node (ref "U$1") (pin "2") (pinfunction "PE3_2") (pintype "bidirectional"))
    )
    (net (code "136") (name "unconnected-(U$1-PE4-Pad3)") (class "Default")
      (node (ref "U$1") (pin "3") (pinfunction "PE4_3") (pintype "bidirectional"))
    )
    (net (code "137") (name "unconnected-(U$1-PE5-Pad4)") (class "Default")
      (node (ref "U$1") (pin "4") (pinfunction "PE5_4") (pintype "bidirectional"))
    )
    (net (code "138") (name "unconnected-(U$1-PE6-Pad5)") (class "Default")
      (node (ref "U$1") (pin "5") (pinfunction "PE6_5") (pintype "bidirectional"))
    )
    (net (code "139") (name "unconnected-(U$1-PE7-Pad38)") (class "Default")
      (node (ref "U$1") (pin "38") (pinfunction "PE7_38") (pintype "bidirectional"))
    )
    (net (code "140") (name "unconnected-(U$1-PE8-Pad39)") (class "Default")
      (node (ref "U$1") (pin "39") (pinfunction "PE8_39") (pintype "bidirectional"))
    )
    (net (code "141") (name "unconnected-(U$1-PE9-Pad40)") (class "Default")
      (node (ref "U$1") (pin "40") (pinfunction "PE9_40") (pintype "bidirectional"))
    )
    (net (code "142") (name "unconnected-(U$1-PE10-Pad41)") (class "Default")
      (node (ref "U$1") (pin "41") (pinfunction "PE10_41") (pintype "bidirectional"))
    )
    (net (code "143") (name "unconnected-(U$1-PE11-Pad42)") (class "Default")
      (node (ref "U$1") (pin "42") (pinfunction "PE11_42") (pintype "bidirectional"))
    )
    (net (code "144") (name "unconnected-(U$1-PE12-Pad43)") (class "Default")
      (node (ref "U$1") (pin "43") (pinfunction "PE12_43") (pintype "bidirectional"))
    )
    (net (code "145") (name "unconnected-(U$1-PE13-Pad44)") (class "Default")
      (node (ref "U$1") (pin "44") (pinfunction "PE13_44") (pintype "bidirectional"))
    )
    (net (code "146") (name "unconnected-(U$1-PE14-Pad45)") (class "Default")
      (node (ref "U$1") (pin "45") (pinfunction "PE14_45") (pintype "bidirectional"))
    )
    (net (code "147") (name "unconnected-(U$1-PE15-Pad46)") (class "Default")
      (node (ref "U$1") (pin "46") (pinfunction "PE15_46") (pintype "bidirectional"))
    )
    (net (code "148") (name "unconnected-(U$1-VBAT-Pad6)") (class "Default")
      (node (ref "U$1") (pin "6") (pinfunction "VBAT_6") (pintype "bidirectional"))
    )
    (net (code "149") (name "unconnected-(U2-AUXOUT-Pad27)") (class "Default")
      (node (ref "U2") (pin "27") (pinfunction "AUXOUT_27") (pintype "tri_state"))
    )
    (net (code "150") (name "unconnected-(U2-ELEC_TEST-Pad33)") (class "Default")
      (node (ref "U2") (pin "33") (pinfunction "ELEC_TEST_33") (pintype "input"))
    )
    (net (code "151") (name "unconnected-(USB1-DM-Pad2)") (class "Default")
      (node (ref "USB1") (pin "2") (pinfunction "DM_2") (pintype "bidirectional"))
    )
    (net (code "152") (name "unconnected-(USB1-DP-Pad3)") (class "Default")
      (node (ref "USB1") (pin "3") (pinfunction "DP_3") (pintype "bidirectional"))
    )
    (net (code "153") (name "unconnected-(USB1-ID-Pad4)") (class "Default")
      (node (ref "USB1") (pin "4") (pinfunction "ID_4") (pintype "bidirectional"))
    )
    (net (code "154") (name "unconnected-(W5500-1-Pad7)") (class "Default")
      (node (ref "W5500-1") (pin "7") (pinfunction "7_7") (pintype "bidirectional"))
    )
    (net (code "155") (name "unconnected-(W5500-1-Pad12)") (class "Default")
      (node (ref "W5500-1") (pin "12") (pinfunction "12_12") (pintype "bidirectional"))
    )
    (net (code "156") (name "unconnected-(W5500-1-Pad13)") (class "Default")
      (node (ref "W5500-1") (pin "13") (pinfunction "13_13") (pintype "bidirectional"))
    )
    (net (code "157") (name "unconnected-(W5500-1-Pad18)") (class "Default")
      (node (ref "W5500-1") (pin "18") (pinfunction "18_18") (pintype "bidirectional"))
    )
    (net (code "158") (name "unconnected-(W5500-1-Pad24)") (class "Default")
      (node (ref "W5500-1") (pin "24") (pinfunction "24_24") (pintype "bidirectional"))
    )
    (net (code "159") (name "unconnected-(W5500-1-Pad26)") (class "Default")
      (node (ref "W5500-1") (pin "26") (pinfunction "26_26") (pintype "bidirectional"))
    )
    (net (code "160") (name "unconnected-(W5500-1-Pad46)") (class "Default")
      (node (ref "W5500-1") (pin "46") (pinfunction "46_46") (pintype "bidirectional"))
    )
    (net (code "161") (name "unconnected-(W5500-1-Pad47)") (class "Default")
      (node (ref "W5500-1") (pin "47") (pinfunction "47_47") (pintype "bidirectional"))
    )
    (net (code "162") (name "unconnected-(Y1-1-Pad4)") (class "Default")
      (node (ref "Y1") (pin "4") (pinfunction "1_4") (pintype "bidirectional"))
    )
    (net (code "163") (name "unconnected-(Y1-3-Pad2)") (class "Default")
      (node (ref "Y1") (pin "2") (pinfunction "3_2") (pintype "bidirectional"))
    )
    (net (code "164") (name "unconnected-(Y2-1-Pad4)") (class "Default")
      (node (ref "Y2") (pin "4") (pinfunction "1_4") (pintype "bidirectional"))
    )
    (net (code "165") (name "unconnected-(Y2-3-Pad2)") (class "Default")
      (node (ref "Y2") (pin "2") (pinfunction "3_2") (pintype "bidirectional"))
    )
  )
)
